# modular-main.net
KiCad netlist of a schematic drawn in EAGLE
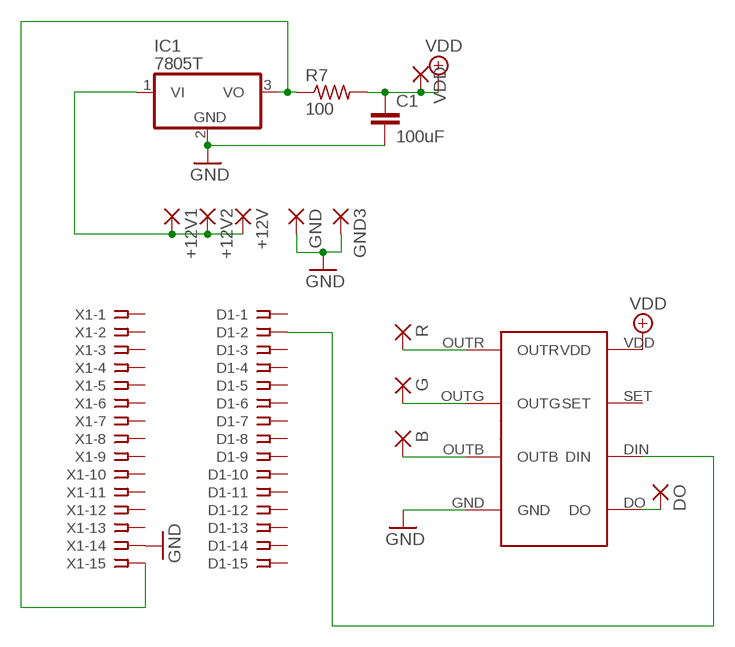
[diagram p0: schematic, sheet 1]

(export (version "E")
  (design (tool "Eeschema 10.0.6"))
  (components
    (comp (ref "+12V")
      (value "SMD5")
      (footprint "eagle-import:SMD2,54-5,08")
      (libsource (lib "eagle-import") (part "SMD5"))
    )
    (comp (ref "+12V1")
      (value "SMD5")
      (footprint "eagle-import:SMD2,54-5,08")
      (libsource (lib "eagle-import") (part "SMD5"))
    )
    (comp (ref "+12V2")
      (value "SMD5")
      (footprint "eagle-import:SMD2,54-5,08")
      (libsource (lib "eagle-import") (part "SMD5"))
    )
    (comp (ref "0")
      (value "WS2811")
      (footprint "eagle-import:SOP8")
      (libsource (lib "eagle-import") (part "WS2811"))
    )
    (comp (ref "B")
      (value "SMD5")
      (footprint "eagle-import:SMD2,54-5,08")
      (libsource (lib "eagle-import") (part "SMD5"))
    )
    (comp (ref "C1")
      (value "100uF")
      (footprint "eagle-import:C0805")
      (libsource (lib "eagle-import") (part "C-EUC0805"))
    )
    (comp (ref "D1")
      (value "SSW-115-02-G-S")
      (footprint "eagle-import:SSW-115-02-G-S")
      (fields (field (name "MF") "Samtec Inc."))
      (libsource (lib "eagle-import") (part "SSW-115-02-G-S"))
    )
    (comp (ref "DO")
      (value "SMD5")
      (footprint "eagle-import:SMD2,54-5,08")
      (libsource (lib "eagle-import") (part "SMD5"))
    )
    (comp (ref "G")
      (value "SMD5")
      (footprint "eagle-import:SMD2,54-5,08")
      (libsource (lib "eagle-import") (part "SMD5"))
    )
    (comp (ref "GND")
      (value "SMD5")
      (footprint "eagle-import:SMD2,54-5,08")
      (libsource (lib "eagle-import") (part "SMD5"))
    )
    (comp (ref "GND3")
      (value "SMD5")
      (footprint "eagle-import:SMD2,54-5,08")
      (libsource (lib "eagle-import") (part "SMD5"))
    )
    (comp (ref "IC1")
      (value "7805T")
      (footprint "eagle-import:TO220H")
      (libsource (lib "eagle-import") (part "78T05"))
    )
    (comp (ref "R")
      (value "SMD5")
      (footprint "eagle-import:SMD2,54-5,08")
      (libsource (lib "eagle-import") (part "SMD5"))
    )
    (comp (ref "R7")
      (value "100")
      (footprint "eagle-import:R0805")
      (libsource (lib "eagle-import") (part "R-US_R0805"))
    )
    (comp (ref "VDD")
      (value "SMD5")
      (footprint "eagle-import:SMD2,54-5,08")
      (libsource (lib "eagle-import") (part "SMD5"))
    )
    (comp (ref "X1")
      (value "SSW-115-02-G-S")
      (footprint "eagle-import:SSW-115-02-G-S")
      (fields (field (name "MF") "Samtec Inc."))
      (libsource (lib "eagle-import") (part "SSW-115-02-G-S"))
    )
  )
  (nets
    (net (code "1") (name "GND") (class "Default")
      (node (ref "0") (pin "GND") (pinfunction "GND_GND") (pintype "bidirectional"))
      (node (ref "C1") (pin "2") (pinfunction "2_2") (pintype "passive"))
      (node (ref "GND") (pin "1") (pinfunction "P_1") (pintype "passive"))
      (node (ref "GND3") (pin "1") (pinfunction "P_1") (pintype "passive"))
      (node (ref "IC1") (pin "2") (pinfunction "GND_2") (pintype "passive"))
      (node (ref "X1") (pin "14") (pinfunction "1_14") (pintype "passive"))
    )
    (net (code "2") (name "Net-(+12V-P)") (class "Default")
      (node (ref "+12V") (pin "1") (pinfunction "P_1") (pintype "passive"))
      (node (ref "+12V1") (pin "1") (pinfunction "P_1") (pintype "passive"))
      (node (ref "+12V2") (pin "1") (pinfunction "P_1") (pintype "passive"))
      (node (ref "IC1") (pin "1") (pinfunction "VI_1") (pintype "input"))
    )
    (net (code "3") (name "Net-(B-P)") (class "Default")
      (node (ref "0") (pin "OUTB") (pinfunction "OUTB_OUTB") (pintype "bidirectional"))
      (node (ref "B") (pin "1") (pinfunction "P_1") (pintype "passive"))
    )
    (net (code "4") (name "Net-(D1H-1)") (class "Default")
      (node (ref "0") (pin "DIN") (pinfunction "DIN_DIN") (pintype "bidirectional"))
      (node (ref "D1") (pin "2") (pinfunction "1_2") (pintype "passive"))
    )
    (net (code "5") (name "Net-(DO-P)") (class "Default")
      (node (ref "0") (pin "DO") (pinfunction "DO_DO") (pintype "bidirectional"))
      (node (ref "DO") (pin "1") (pinfunction "P_1") (pintype "passive"))
    )
    (net (code "6") (name "Net-(G-P)") (class "Default")
      (node (ref "0") (pin "OUTG") (pinfunction "OUTG_OUTG") (pintype "bidirectional"))
      (node (ref "G") (pin "1") (pinfunction "P_1") (pintype "passive"))
    )
    (net (code "7") (name "Net-(IC1-VO)") (class "Default")
      (node (ref "IC1") (pin "3") (pinfunction "VO_3") (pintype "passive"))
      (node (ref "R7") (pin "1") (pinfunction "1_1") (pintype "passive"))
      (node (ref "X1") (pin "15") (pinfunction "1_15") (pintype "passive"))
    )
    (net (code "8") (name "Net-(R-P)") (class "Default")
      (node (ref "0") (pin "OUTR") (pinfunction "OUTR_OUTR") (pintype "bidirectional"))
      (node (ref "R") (pin "1") (pinfunction "P_1") (pintype "passive"))
    )
    (net (code "9") (name "VDD") (class "Default")
      (node (ref "0") (pin "VDD") (pinfunction "VDD_VDD") (pintype "bidirectional"))
      (node (ref "C1") (pin "1") (pinfunction "1_1") (pintype "passive"))
      (node (ref "R7") (pin "2") (pinfunction "2_2") (pintype "passive"))
      (node (ref "VDD") (pin "1") (pinfunction "P_1") (pintype "passive"))
    )
    (net (code "10") (name "unconnected-(0-PadSET)") (class "Default")
      (node (ref "0") (pin "SET") (pinfunction "SET_SET") (pintype "bidirectional"))
    )
    (net (code "11") (name "unconnected-(D1-Pad1)") (class "Default")
      (node (ref "D1") (pin "1") (pinfunction "1_1") (pintype "passive"))
    )
    (net (code "12") (name "unconnected-(D1B-1-Pad10)") (class "Default")
      (node (ref "D1") (pin "10") (pinfunction "1_10") (pintype "passive"))
    )
    (net (code "13") (name "unconnected-(D1C-1-Pad11)") (class "Default")
      (node (ref "D1") (pin "11") (pinfunction "1_11") (pintype "passive"))
    )
    (net (code "14") (name "unconnected-(D1D-1-Pad12)") (class "Default")
      (node (ref "D1") (pin "12") (pinfunction "1_12") (pintype "passive"))
    )
    (net (code "15") (name "unconnected-(D1E-1-Pad13)") (class "Default")
      (node (ref "D1") (pin "13") (pinfunction "1_13") (pintype "passive"))
    )
    (net (code "16") (name "unconnected-(D1F-1-Pad14)") (class "Default")
      (node (ref "D1") (pin "14") (pinfunction "1_14") (pintype "passive"))
    )
    (net (code "17") (name "unconnected-(D1G-1-Pad15)") (class "Default")
      (node (ref "D1") (pin "15") (pinfunction "1_15") (pintype "passive"))
    )
    (net (code "18") (name "unconnected-(D1I-1-Pad3)") (class "Default")
      (node (ref "D1") (pin "3") (pinfunction "1_3") (pintype "passive"))
    )
    (net (code "19") (name "unconnected-(D1J-1-Pad4)") (class "Default")
      (node (ref "D1") (pin "4") (pinfunction "1_4") (pintype "passive"))
    )
    (net (code "20") (name "unconnected-(D1K-1-Pad5)") (class "Default")
      (node (ref "D1") (pin "5") (pinfunction "1_5") (pintype "passive"))
    )
    (net (code "21") (name "unconnected-(D1L-1-Pad6)") (class "Default")
      (node (ref "D1") (pin "6") (pinfunction "1_6") (pintype "passive"))
    )
    (net (code "22") (name "unconnected-(D1M-1-Pad7)") (class "Default")
      (node (ref "D1") (pin "7") (pinfunction "1_7") (pintype "passive"))
    )
    (net (code "23") (name "unconnected-(D1N-1-Pad8)") (class "Default")
      (node (ref "D1") (pin "8") (pinfunction "1_8") (pintype "passive"))
    )
    (net (code "24") (name "unconnected-(D1O-1-Pad9)") (class "Default")
      (node (ref "D1") (pin "9") (pinfunction "1_9") (pintype "passive"))
    )
    (net (code "25") (name "unconnected-(X1-Pad1)") (class "Default")
      (node (ref "X1") (pin "1") (pinfunction "1_1") (pintype "passive"))
    )
    (net (code "26") (name "unconnected-(X1B-1-Pad10)") (class "Default")
      (node (ref "X1") (pin "10") (pinfunction "1_10") (pintype "passive"))
    )
    (net (code "27") (name "unconnected-(X1C-1-Pad11)") (class "Default")
      (node (ref "X1") (pin "11") (pinfunction "1_11") (pintype "passive"))
    )
    (net (code "28") (name "unconnected-(X1D-1-Pad12)") (class "Default")
      (node (ref "X1") (pin "12") (pinfunction "1_12") (pintype "passive"))
    )
    (net (code "29") (name "unconnected-(X1E-1-Pad13)") (class "Default")
      (node (ref "X1") (pin "13") (pinfunction "1_13") (pintype "passive"))
    )
    (net (code "30") (name "unconnected-(X1H-1-Pad2)") (class "Default")
      (node (ref "X1") (pin "2") (pinfunction "1_2") (pintype "passive"))
    )
    (net (code "31") (name "unconnected-(X1I-1-Pad3)") (class "Default")
      (node (ref "X1") (pin "3") (pinfunction "1_3") (pintype "passive"))
    )
    (net (code "32") (name "unconnected-(X1J-1-Pad4)") (class "Default")
      (node (ref "X1") (pin "4") (pinfunction "1_4") (pintype "passive"))
    )
    (net (code "33") (name "unconnected-(X1K-1-Pad5)") (class "Default")
      (node (ref "X1") (pin "5") (pinfunction "1_5") (pintype "passive"))
    )
    (net (code "34") (name "unconnected-(X1L-1-Pad6)") (class "Default")
      (node (ref "X1") (pin "6") (pinfunction "1_6") (pintype "passive"))
    )
    (net (code "35") (name "unconnected-(X1M-1-Pad7)") (class "Default")
      (node (ref "X1") (pin "7") (pinfunction "1_7") (pintype "passive"))
    )
    (net (code "36") (name "unconnected-(X1N-1-Pad8)") (class "Default")
      (node (ref "X1") (pin "8") (pinfunction "1_8") (pintype "passive"))
    )
    (net (code "37") (name "unconnected-(X1O-1-Pad9)") (class "Default")
      (node (ref "X1") (pin "9") (pinfunction "1_9") (pintype "passive"))
    )
  )
)
